# KEY.net
KiCad netlist of a schematic drawn in Altium Designer
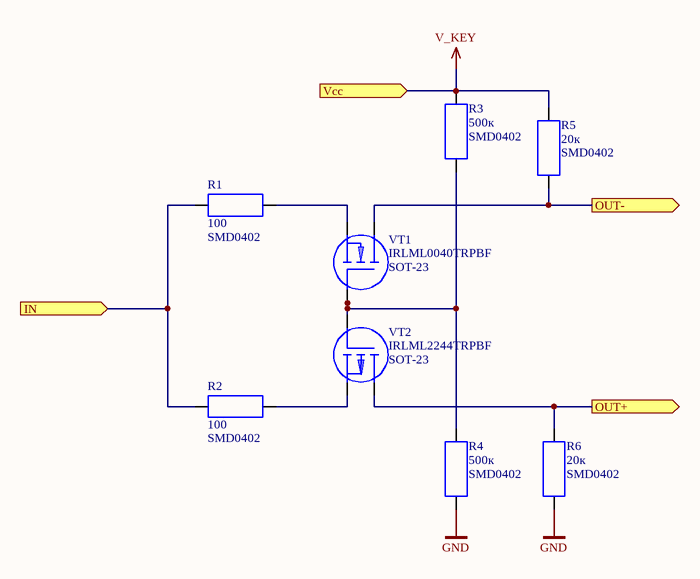
[diagram p0: KEY.SchDoc]

(export (version "E")
  (design (tool "Eeschema 10.0.6"))
  (components
    (comp (ref "R1")
      (value "100")
      (footprint "SMD0402(1608)")
      (fields (field (name "PACKAGE") "SMD0402"))
      (libsource (lib "MechanikLibrary") (part "R_0402"))
    )
    (comp (ref "R2")
      (value "100")
      (footprint "SMD0402(1608)")
      (fields (field (name "PACKAGE") "SMD0402"))
      (libsource (lib "MechanikLibrary") (part "R_0402"))
    )
    (comp (ref "R3")
      (value "500к")
      (footprint "SMD0402(1608)")
      (fields (field (name "PACKAGE") "SMD0402"))
      (libsource (lib "MechanikLibrary") (part "R_0402"))
    )
    (comp (ref "R4")
      (value "500к")
      (footprint "SMD0402(1608)")
      (fields (field (name "PACKAGE") "SMD0402"))
      (libsource (lib "MechanikLibrary") (part "R_0402"))
    )
    (comp (ref "R5")
      (value "20к")
      (footprint "SMD0402(1608)")
      (fields (field (name "PACKAGE") "SMD0402"))
      (libsource (lib "MechanikLibrary") (part "R_0402"))
    )
    (comp (ref "R6")
      (value "20к")
      (footprint "SMD0402(1608)")
      (fields (field (name "PACKAGE") "SMD0402"))
      (libsource (lib "MechanikLibrary") (part "R_0402"))
    )
    (comp (ref "VT1")
      (value "IRLML0040TRPBF")
      (footprint "SOT23-3")
      (fields (field (name "PACKAGE") "SOT-23"))
      (libsource (lib "MechanikLibrary") (part "VT_N_MOSFET_SOT23_3"))
    )
    (comp (ref "VT2")
      (value "IRLML2244TRPBF")
      (footprint "SOT23-3")
      (fields (field (name "PACKAGE") "SOT-23"))
      (libsource (lib "MechanikLibrary") (part "VT_P_MOSFET_SOT23_3"))
    )
  )
  (nets
    (net (code "1") (name "/IN") (class "Default")
      (node (ref "R1") (pin "2") (pintype "passive"))
      (node (ref "R2") (pin "2") (pintype "passive"))
    )
    (net (code "2") (name "/OUT+") (class "Default")
      (node (ref "R6") (pin "1") (pintype "passive"))
      (node (ref "VT2") (pin "3") (pintype "passive"))
    )
    (net (code "3") (name "/OUT-") (class "Default")
      (node (ref "R5") (pin "2") (pintype "passive"))
      (node (ref "VT1") (pin "3") (pintype "passive"))
    )
    (net (code "4") (name "GND") (class "Default")
      (node (ref "R4") (pin "2") (pintype "passive"))
      (node (ref "R6") (pin "2") (pintype "passive"))
    )
    (net (code "5") (name "Net-(R1-Pad1)") (class "Default")
      (node (ref "R1") (pin "1") (pintype "passive"))
      (node (ref "VT1") (pin "2") (pintype "passive"))
    )
    (net (code "6") (name "Net-(R2-Pad1)") (class "Default")
      (node (ref "R2") (pin "1") (pintype "passive"))
      (node (ref "VT2") (pin "2") (pintype "passive"))
    )
    (net (code "7") (name "Net-(R3-Pad2)") (class "Default")
      (node (ref "R3") (pin "2") (pintype "passive"))
      (node (ref "R4") (pin "1") (pintype "passive"))
      (node (ref "VT1") (pin "1") (pintype "passive"))
      (node (ref "VT2") (pin "1") (pintype "passive"))
    )
    (net (code "8") (name "V_KEY") (class "Default")
      (node (ref "R3") (pin "1") (pintype "passive"))
      (node (ref "R5") (pin "1") (pintype "passive"))
    )
  )
)
